# FuTseYi_STM32-Health-Band__hardware_sche.net
KiCad netlist of a schematic drawn in Altium Designer
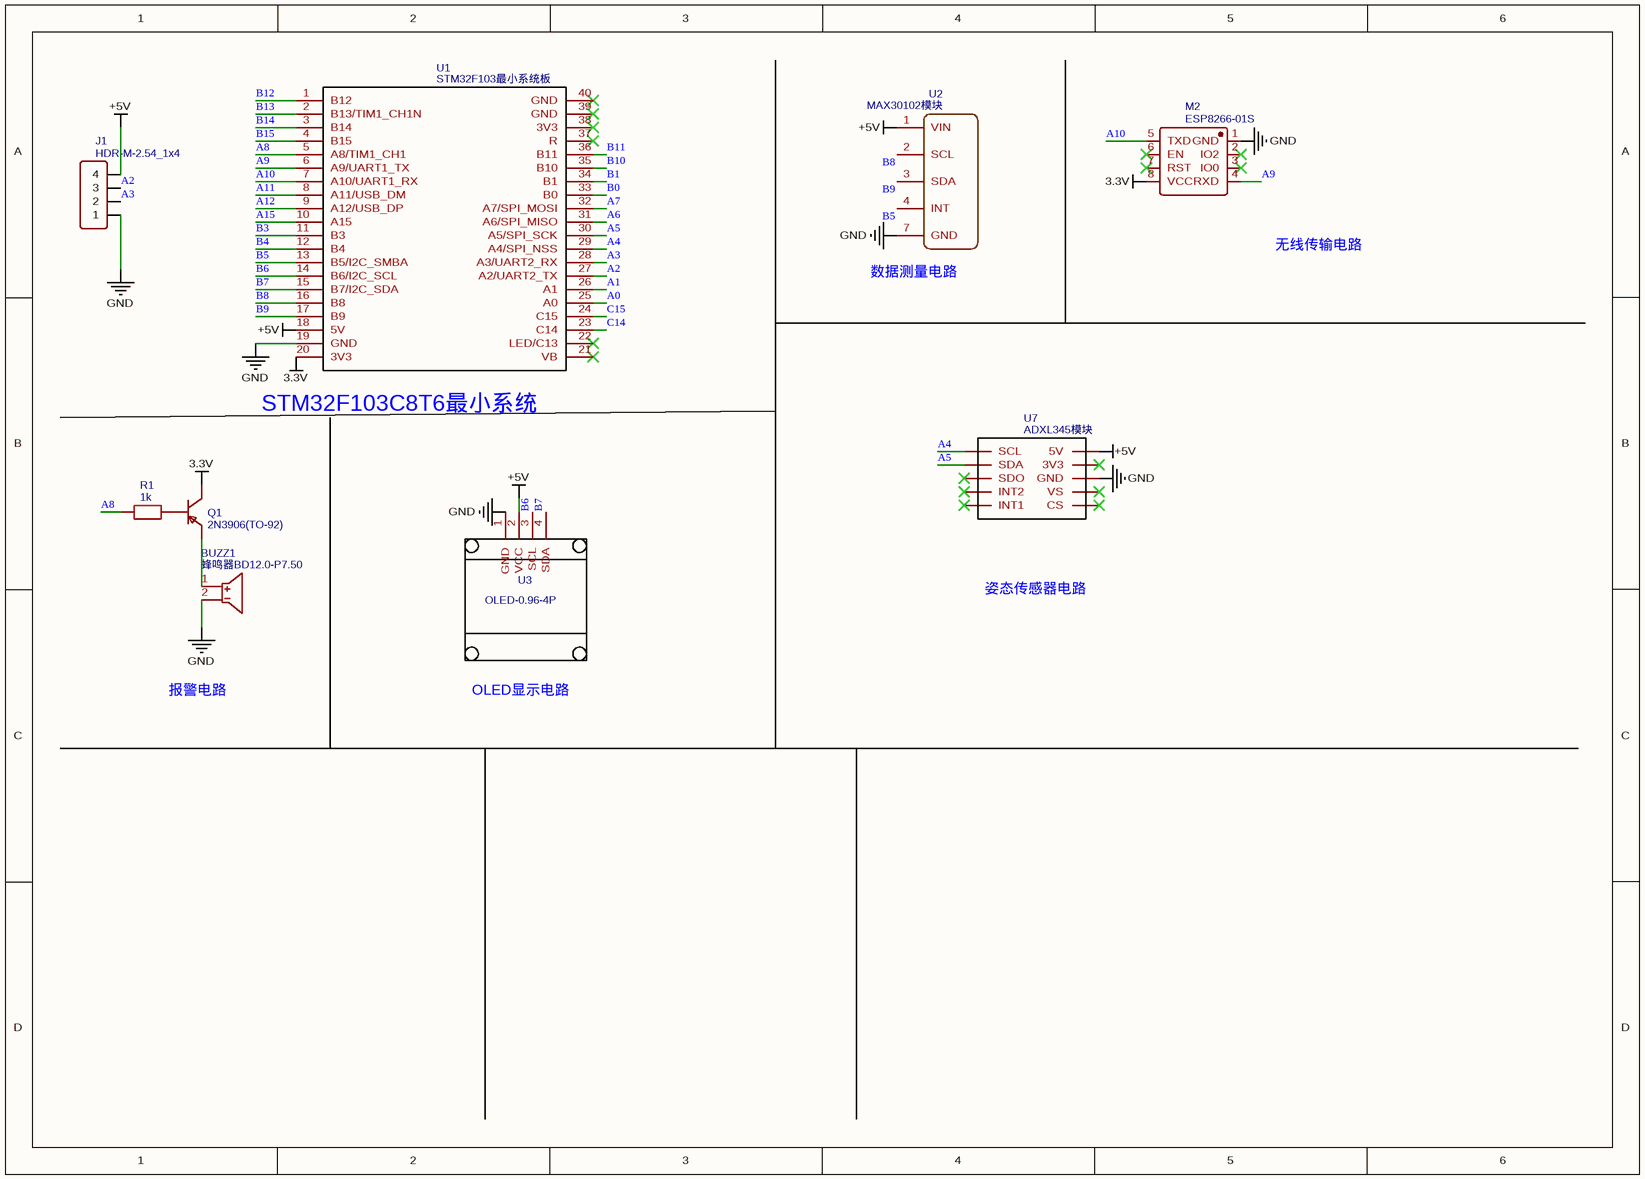
[diagram p0: FuTseYi_STM32-Health-Band__hardware_schematics__AD版本.schdoc]

(export (version "E")
  (design (tool "Eeschema 10.0.6"))
  (components
    (comp (ref "BUZZ1")
      (value "蜂鸣器BD12.0-P7.50")
      (fields (field (name "BOM_SUPPLIER PART") "C9900003117") (field (name "CONTRIBUTOR") "LCSC"))
      (libsource (lib "altium-import") (part "root_0_蜂鸣器BD12.0-P7.50_"))
    )
    (comp (ref "J1")
      (value "HDR-M-2.54_1x4")
      (fields (field (name "BOM_SUPPLIER PART") "C124378") (field (name "CONTRIBUTOR") "LCEDA_Lib"))
      (libsource (lib "altium-import") (part "root_2_HDR-M-2.54_1x4_"))
    )
    (comp (ref "M2")
      (value "ESP8266-01S")
      (fields (field (name "CONTRIBUTOR") "lmfyy1314"))
      (libsource (lib "altium-import") (part "root_0_ESP8266-01S_"))
    )
    (comp (ref "Q1")
      (value "2N3906(TO-92)")
      (fields
        (field (name "BOM_MANUFACTURER PART") "2N3906")
        (field (name "BOM_SUPPLIER PART") "C9809")
        (field (name "CONTRIBUTOR") "LCEDA_Lib")
      )
      (libsource (lib "altium-import") (part "root_0_2N3906(TO-92)_"))
    )
    (comp (ref "R1")
      (value "1k")
      (fields (field (name "CONTRIBUTOR") "LCEDA_Lib"))
      (libsource (lib "altium-import") (part "root_0_1k_"))
    )
    (comp (ref "U1")
      (value "STM32F103最小系统板")
      (fields (field (name "CONTRIBUTOR") "largestbrush"))
      (libsource (lib "altium-import") (part "root_0_STM32F103最小系统板_"))
    )
    (comp (ref "U2")
      (value "MAX30102模块")
      (fields (field (name "CONTRIBUTOR") "TanAifeng"))
      (libsource (lib "altium-import") (part "root_0_MAX30102模块_"))
    )
    (comp (ref "U3")
      (value "OLED-0.96-4P")
      (fields
        (field (name "BOM_MANUFACTURER PART") "oled-0.96-4p-spi")
        (field (name "BOM_SUPPLIER PART") "undefined")
        (field (name "CONTRIBUTOR") "gnawnij")
      )
      (libsource (lib "altium-import") (part "root_0_OLED-0.96-4P_"))
    )
    (comp (ref "U7")
      (value "ADXL345模块")
      (fields (field (name "CONTRIBUTOR") "hengyong"))
      (libsource (lib "altium-import") (part "root_0_ADXL345模块_"))
    )
  )
  (nets
    (net (code "1") (name "+5V") (class "Default")
      (node (ref "J1") (pin "4") (pinfunction "4_4") (pintype "passive"))
      (node (ref "U1") (pin "18") (pinfunction "5V_18") (pintype "passive"))
      (node (ref "U2") (pin "1") (pinfunction "VIN_1") (pintype "passive"))
      (node (ref "U3") (pin "2") (pinfunction "VCC_2") (pintype "passive"))
      (node (ref "U7") (pin "10") (pinfunction "5V_10") (pintype "passive"))
    )
    (net (code "2") (name "/A0") (class "Default")
      (node (ref "U1") (pin "25") (pinfunction "A0_25") (pintype "passive"))
    )
    (net (code "3") (name "/A1") (class "Default")
      (node (ref "U1") (pin "26") (pinfunction "A1_26") (pintype "passive"))
    )
    (net (code "4") (name "/A2") (class "Default")
      (node (ref "J1") (pin "3") (pinfunction "3_3") (pintype "passive"))
      (node (ref "U1") (pin "27") (pinfunction "A2/UART2_TX_27") (pintype "passive"))
    )
    (net (code "5") (name "/A3") (class "Default")
      (node (ref "J1") (pin "2") (pinfunction "2_2") (pintype "passive"))
      (node (ref "U1") (pin "28") (pinfunction "A3/UART2_RX_28") (pintype "passive"))
    )
    (net (code "6") (name "/A4") (class "Default")
      (node (ref "U1") (pin "29") (pinfunction "A4/SPI_NSS_29") (pintype "passive"))
      (node (ref "U7") (pin "1") (pinfunction "SCL_1") (pintype "passive"))
    )
    (net (code "7") (name "/A5") (class "Default")
      (node (ref "U1") (pin "30") (pinfunction "A5/SPI_SCK_30") (pintype "passive"))
      (node (ref "U7") (pin "2") (pinfunction "SDA_2") (pintype "passive"))
    )
    (net (code "8") (name "/A6") (class "Default")
      (node (ref "U1") (pin "31") (pinfunction "A6/SPI_MISO_31") (pintype "passive"))
    )
    (net (code "9") (name "/A7") (class "Default")
      (node (ref "U1") (pin "32") (pinfunction "A7/SPI_MOSI_32") (pintype "passive"))
    )
    (net (code "10") (name "/A8") (class "Default")
      (node (ref "R1") (pin "1") (pinfunction "1_1") (pintype "passive"))
      (node (ref "U1") (pin "5") (pinfunction "A8/TIM1_CH1_5") (pintype "passive"))
    )
    (net (code "11") (name "/A9") (class "Default")
      (node (ref "M2") (pin "4") (pinfunction "RXD_4") (pintype "passive"))
      (node (ref "U1") (pin "6") (pinfunction "A9/UART1_TX_6") (pintype "passive"))
    )
    (net (code "12") (name "/A10") (class "Default")
      (node (ref "M2") (pin "5") (pinfunction "TXD_5") (pintype "passive"))
      (node (ref "U1") (pin "7") (pinfunction "A10/UART1_RX_7") (pintype "passive"))
    )
    (net (code "13") (name "/A11") (class "Default")
      (node (ref "U1") (pin "8") (pinfunction "A11/USB_DM_8") (pintype "passive"))
    )
    (net (code "14") (name "/A12") (class "Default")
      (node (ref "U1") (pin "9") (pinfunction "A12/USB_DP_9") (pintype "passive"))
    )
    (net (code "15") (name "/A15") (class "Default")
      (node (ref "U1") (pin "10") (pinfunction "A15_10") (pintype "passive"))
    )
    (net (code "16") (name "/B0") (class "Default")
      (node (ref "U1") (pin "33") (pinfunction "B0_33") (pintype "passive"))
    )
    (net (code "17") (name "/B1") (class "Default")
      (node (ref "U1") (pin "34") (pinfunction "B1_34") (pintype "passive"))
    )
    (net (code "18") (name "/B3") (class "Default")
      (node (ref "U1") (pin "11") (pinfunction "B3_11") (pintype "passive"))
    )
    (net (code "19") (name "/B4") (class "Default")
      (node (ref "U1") (pin "12") (pinfunction "B4_12") (pintype "passive"))
    )
    (net (code "20") (name "/B5") (class "Default")
      (node (ref "U1") (pin "13") (pinfunction "B5/I2C_SMBA_13") (pintype "passive"))
      (node (ref "U2") (pin "4") (pinfunction "INT_4") (pintype "passive"))
    )
    (net (code "21") (name "/B6") (class "Default")
      (node (ref "U1") (pin "14") (pinfunction "B6/I2C_SCL_14") (pintype "passive"))
      (node (ref "U3") (pin "3") (pinfunction "SCL_3") (pintype "passive"))
    )
    (net (code "22") (name "/B7") (class "Default")
      (node (ref "U1") (pin "15") (pinfunction "B7/I2C_SDA_15") (pintype "passive"))
      (node (ref "U3") (pin "4") (pinfunction "SDA_4") (pintype "passive"))
    )
    (net (code "23") (name "/B8") (class "Default")
      (node (ref "U1") (pin "16") (pinfunction "B8_16") (pintype "passive"))
      (node (ref "U2") (pin "2") (pinfunction "SCL_2") (pintype "passive"))
    )
    (net (code "24") (name "/B9") (class "Default")
      (node (ref "U1") (pin "17") (pinfunction "B9_17") (pintype "passive"))
      (node (ref "U2") (pin "3") (pinfunction "SDA_3") (pintype "passive"))
    )
    (net (code "25") (name "/B10") (class "Default")
      (node (ref "U1") (pin "35") (pinfunction "B10_35") (pintype "passive"))
    )
    (net (code "26") (name "/B11") (class "Default")
      (node (ref "U1") (pin "36") (pinfunction "B11_36") (pintype "passive"))
    )
    (net (code "27") (name "/B12") (class "Default")
      (node (ref "U1") (pin "1") (pinfunction "B12_1") (pintype "passive"))
    )
    (net (code "28") (name "/B13") (class "Default")
      (node (ref "U1") (pin "2") (pinfunction "B13/TIM1_CH1N_2") (pintype "passive"))
    )
    (net (code "29") (name "/B14") (class "Default")
      (node (ref "U1") (pin "3") (pinfunction "B14_3") (pintype "passive"))
    )
    (net (code "30") (name "/B15") (class "Default")
      (node (ref "U1") (pin "4") (pinfunction "B15_4") (pintype "passive"))
    )
    (net (code "31") (name "/C14") (class "Default")
      (node (ref "U1") (pin "23") (pinfunction "C14_23") (pintype "passive"))
    )
    (net (code "32") (name "/C15") (class "Default")
      (node (ref "U1") (pin "24") (pinfunction "C15_24") (pintype "passive"))
    )
    (net (code "33") (name "3.3V") (class "Default")
      (node (ref "M2") (pin "8") (pinfunction "VCC_8") (pintype "passive"))
      (node (ref "Q1") (pin "3") (pinfunction "C_3") (pintype "passive"))
      (node (ref "U1") (pin "20") (pinfunction "3V3_20") (pintype "passive"))
    )
    (net (code "34") (name "GND") (class "Default")
      (node (ref "BUZZ1") (pin "2") (pinfunction "2_2") (pintype "passive"))
      (node (ref "J1") (pin "1") (pinfunction "1_1") (pintype "passive"))
      (node (ref "M2") (pin "1") (pinfunction "GND_1") (pintype "passive"))
      (node (ref "U1") (pin "19") (pinfunction "GND_19") (pintype "passive"))
      (node (ref "U2") (pin "7") (pinfunction "GND_7") (pintype "passive"))
      (node (ref "U3") (pin "1") (pinfunction "GND_1") (pintype "passive"))
      (node (ref "U7") (pin "8") (pinfunction "GND_8") (pintype "passive"))
    )
    (net (code "35") (name "Net-(Q1-B)") (class "Default")
      (node (ref "Q1") (pin "2") (pinfunction "B_2") (pintype "passive"))
      (node (ref "R1") (pin "2") (pinfunction "2_2") (pintype "passive"))
    )
    (net (code "36") (name "Net-(Q1-E)") (class "Default")
      (node (ref "BUZZ1") (pin "1") (pinfunction "1_1") (pintype "passive"))
      (node (ref "Q1") (pin "1") (pinfunction "E_1") (pintype "passive"))
    )
    (net (code "37") (name "unconnected-(M2-EN-Pad6)") (class "Default")
      (node (ref "M2") (pin "6") (pinfunction "EN_6") (pintype "passive+no_connect"))
    )
    (net (code "38") (name "unconnected-(M2-IO0-Pad3)") (class "Default")
      (node (ref "M2") (pin "3") (pinfunction "IO0_3") (pintype "passive+no_connect"))
    )
    (net (code "39") (name "unconnected-(M2-IO2-Pad2)") (class "Default")
      (node (ref "M2") (pin "2") (pinfunction "IO2_2") (pintype "passive+no_connect"))
    )
    (net (code "40") (name "unconnected-(M2-RST-Pad7)") (class "Default")
      (node (ref "M2") (pin "7") (pinfunction "RST_7") (pintype "passive+no_connect"))
    )
    (net (code "41") (name "unconnected-(U1-3V3-Pad38)") (class "Default")
      (node (ref "U1") (pin "38") (pinfunction "3V3_38") (pintype "passive+no_connect"))
    )
    (net (code "42") (name "unconnected-(U1-GND-Pad39)") (class "Default")
      (node (ref "U1") (pin "39") (pinfunction "GND_39") (pintype "passive+no_connect"))
    )
    (net (code "43") (name "unconnected-(U1-GND-Pad40)") (class "Default")
      (node (ref "U1") (pin "40") (pinfunction "GND_40") (pintype "passive+no_connect"))
    )
    (net (code "44") (name "unconnected-(U1-LED{slash}C13-Pad22)") (class "Default")
      (node (ref "U1") (pin "22") (pinfunction "LED/C13_22") (pintype "passive+no_connect"))
    )
    (net (code "45") (name "unconnected-(U1-R-Pad37)") (class "Default")
      (node (ref "U1") (pin "37") (pinfunction "R_37") (pintype "passive+no_connect"))
    )
    (net (code "46") (name "unconnected-(U1-VB-Pad21)") (class "Default")
      (node (ref "U1") (pin "21") (pinfunction "VB_21") (pintype "passive+no_connect"))
    )
    (net (code "47") (name "unconnected-(U7-3V3-Pad9)") (class "Default")
      (node (ref "U7") (pin "9") (pinfunction "3V3_9") (pintype "passive+no_connect"))
    )
    (net (code "48") (name "unconnected-(U7-CS-Pad6)") (class "Default")
      (node (ref "U7") (pin "6") (pinfunction "CS_6") (pintype "passive+no_connect"))
    )
    (net (code "49") (name "unconnected-(U7-INT1-Pad5)") (class "Default")
      (node (ref "U7") (pin "5") (pinfunction "INT1_5") (pintype "passive+no_connect"))
    )
    (net (code "50") (name "unconnected-(U7-INT2-Pad4)") (class "Default")
      (node (ref "U7") (pin "4") (pinfunction "INT2_4") (pintype "passive+no_connect"))
    )
    (net (code "51") (name "unconnected-(U7-SDO-Pad3)") (class "Default")
      (node (ref "U7") (pin "3") (pinfunction "SDO_3") (pintype "passive+no_connect"))
    )
    (net (code "52") (name "unconnected-(U7-VS-Pad7)") (class "Default")
      (node (ref "U7") (pin "7") (pinfunction "VS_7") (pintype "passive+no_connect"))
    )
  )
)
